# RxDuino_Rev4b.net
KiCad netlist of a schematic drawn in EAGLE
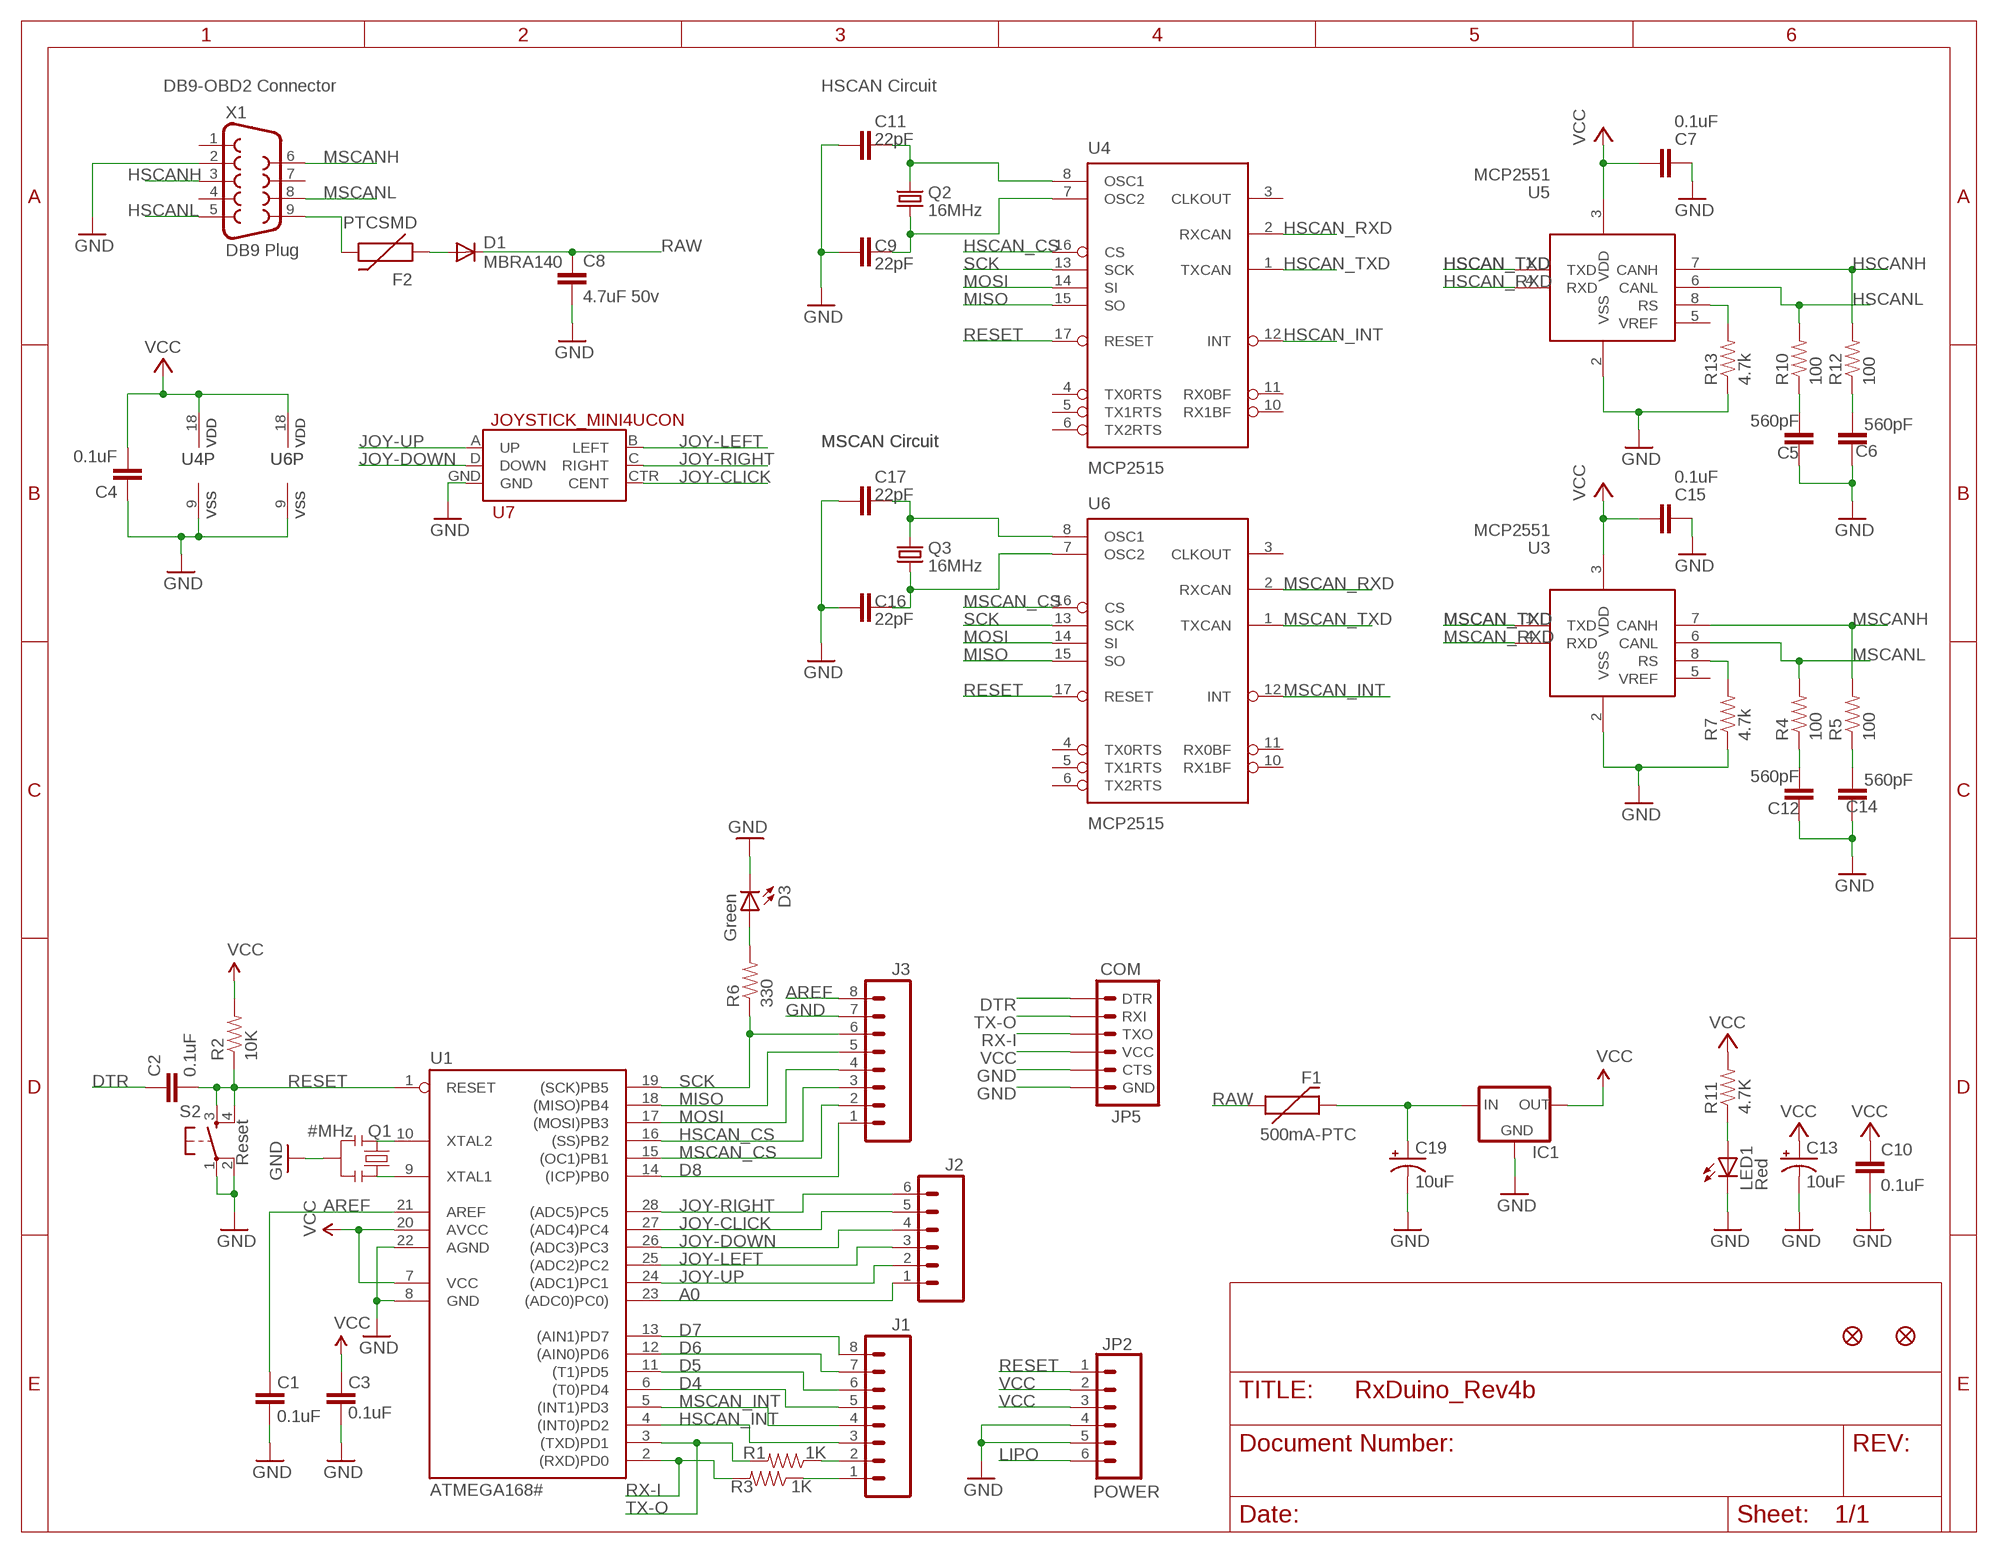
[diagram p0: schematic, sheet 1]

(export (version "E")
  (design (tool "Eeschema 10.0.6"))
  (components
    (comp (ref "C1")
      (value "0.1uF")
      (footprint "eagle-import:1206")
      (libsource (lib "eagle-import") (part "CAP1206"))
    )
    (comp (ref "C2")
      (value "0.1uF")
      (footprint "eagle-import:1206")
      (libsource (lib "eagle-import") (part "CAP1206"))
    )
    (comp (ref "C3")
      (value "0.1uF")
      (footprint "eagle-import:1206")
      (libsource (lib "eagle-import") (part "CAP1206"))
    )
    (comp (ref "C4")
      (value "0.1uF")
      (footprint "eagle-import:1206")
      (libsource (lib "eagle-import") (part "CAP1206"))
    )
    (comp (ref "C5")
      (value "560pF")
      (footprint "eagle-import:1206")
      (libsource (lib "eagle-import") (part "CAP1206"))
    )
    (comp (ref "C6")
      (value "560pF")
      (footprint "eagle-import:1206")
      (libsource (lib "eagle-import") (part "CAP1206"))
    )
    (comp (ref "C7")
      (value "0.1uF")
      (footprint "eagle-import:1206")
      (libsource (lib "eagle-import") (part "CAP1206"))
    )
    (comp (ref "C8")
      (value "4.7uF 50v")
      (footprint "eagle-import:1206")
      (libsource (lib "eagle-import") (part "CAP1206"))
    )
    (comp (ref "C9")
      (value "22pF")
      (footprint "eagle-import:1206")
      (libsource (lib "eagle-import") (part "CAP1206"))
    )
    (comp (ref "C10")
      (value "0.1uF")
      (footprint "eagle-import:1206")
      (libsource (lib "eagle-import") (part "CAP1206"))
    )
    (comp (ref "C11")
      (value "22pF")
      (footprint "eagle-import:1206")
      (libsource (lib "eagle-import") (part "CAP1206"))
    )
    (comp (ref "C12")
      (value "560pF")
      (footprint "eagle-import:1206")
      (libsource (lib "eagle-import") (part "CAP1206"))
    )
    (comp (ref "C13")
      (value "10uF")
      (footprint "eagle-import:PANASONIC_E")
      (libsource (lib "eagle-import") (part "CAP_POLE"))
    )
    (comp (ref "C14")
      (value "560pF")
      (footprint "eagle-import:1206")
      (libsource (lib "eagle-import") (part "CAP1206"))
    )
    (comp (ref "C15")
      (value "0.1uF")
      (footprint "eagle-import:1206")
      (libsource (lib "eagle-import") (part "CAP1206"))
    )
    (comp (ref "C16")
      (value "22pF")
      (footprint "eagle-import:1206")
      (libsource (lib "eagle-import") (part "CAP1206"))
    )
    (comp (ref "C17")
      (value "22pF")
      (footprint "eagle-import:1206")
      (libsource (lib "eagle-import") (part "CAP1206"))
    )
    (comp (ref "C19")
      (value "10uF")
      (footprint "eagle-import:PANASONIC_E")
      (libsource (lib "eagle-import") (part "CAP_POLE"))
    )
    (comp (ref "D1")
      (value "MBRA140")
      (footprint "eagle-import:SMA-DIODE")
      (libsource (lib "eagle-import") (part "DIODESMA"))
    )
    (comp (ref "D3")
      (value "Green")
      (footprint "eagle-import:LED-1206")
      (libsource (lib "eagle-import") (part "LED1206"))
    )
    (comp (ref "F1")
      (value "500mA-PTC")
      (footprint "eagle-import:PTC-1206")
      (libsource (lib "eagle-import") (part "PTCSMD"))
    )
    (comp (ref "F2")
      (value "PTCSMD")
      (footprint "eagle-import:PTC-1206")
      (libsource (lib "eagle-import") (part "PTCSMD"))
    )
    (comp (ref "IC1")
      (value "V_REG_78XX-TO-220")
      (footprint "eagle-import:TO-220-ALT")
      (libsource (lib "eagle-import") (part "V_REG_78XX-TO-220"))
    )
    (comp (ref "J1")
      (value "M08")
      (footprint "eagle-import:1X08")
      (libsource (lib "eagle-import") (part "M08"))
    )
    (comp (ref "J2")
      (value "M06SIP")
      (footprint "eagle-import:1X06")
      (libsource (lib "eagle-import") (part "M06SIP"))
    )
    (comp (ref "J3")
      (value "M08")
      (footprint "eagle-import:1X08")
      (libsource (lib "eagle-import") (part "M08"))
    )
    (comp (ref "JP2")
      (value "POWER")
      (footprint "eagle-import:1X06")
      (libsource (lib "eagle-import") (part "M06SIP"))
    )
    (comp (ref "JP5")
      (value "COM")
      (footprint "eagle-import:1X06")
      (libsource (lib "eagle-import") (part "ARDUINO_SERIAL_PROGRAMPTH"))
    )
    (comp (ref "LED1")
      (value "Red")
      (footprint "eagle-import:LED-1206")
      (libsource (lib "eagle-import") (part "LED1206"))
    )
    (comp (ref "Q1")
      (value "#MHz")
      (footprint "eagle-import:RESONATOR-PTH")
      (libsource (lib "eagle-import") (part "RESONATORPTH"))
    )
    (comp (ref "Q2")
      (value "16MHz")
      (footprint "eagle-import:HC49US")
      (libsource (lib "eagle-import") (part "CRYSTALHC49US"))
    )
    (comp (ref "Q3")
      (value "16MHz")
      (footprint "eagle-import:HC49US")
      (libsource (lib "eagle-import") (part "CRYSTALHC49US"))
    )
    (comp (ref "R1")
      (value "1K")
      (footprint "eagle-import:1206")
      (libsource (lib "eagle-import") (part "RESISTOR1206"))
    )
    (comp (ref "R2")
      (value "10K")
      (footprint "eagle-import:1206")
      (libsource (lib "eagle-import") (part "RESISTOR1206"))
    )
    (comp (ref "R3")
      (value "1K")
      (footprint "eagle-import:1206")
      (libsource (lib "eagle-import") (part "RESISTOR1206"))
    )
    (comp (ref "R4")
      (value "100")
      (footprint "eagle-import:1206")
      (libsource (lib "eagle-import") (part "RESISTOR1206"))
    )
    (comp (ref "R5")
      (value "100")
      (footprint "eagle-import:1206")
      (libsource (lib "eagle-import") (part "RESISTOR1206"))
    )
    (comp (ref "R6")
      (value "330")
      (footprint "eagle-import:1206")
      (libsource (lib "eagle-import") (part "RESISTOR1206"))
    )
    (comp (ref "R7")
      (value "4.7k")
      (footprint "eagle-import:1206")
      (libsource (lib "eagle-import") (part "RESISTOR1206"))
    )
    (comp (ref "R10")
      (value "100")
      (footprint "eagle-import:1206")
      (libsource (lib "eagle-import") (part "RESISTOR1206"))
    )
    (comp (ref "R11")
      (value "4.7K")
      (footprint "eagle-import:1206")
      (libsource (lib "eagle-import") (part "RESISTOR1206"))
    )
    (comp (ref "R12")
      (value "100")
      (footprint "eagle-import:1206")
      (libsource (lib "eagle-import") (part "RESISTOR1206"))
    )
    (comp (ref "R13")
      (value "4.7k")
      (footprint "eagle-import:1206")
      (libsource (lib "eagle-import") (part "RESISTOR1206"))
    )
    (comp (ref "S2")
      (value "Reset")
      (footprint "eagle-import:TACTILE_SWITCH_SMD")
      (libsource (lib "eagle-import") (part "TAC_SWITCHSND"))
    )
    (comp (ref "U$2")
      (value "FIDUCIAL1X2")
      (footprint "eagle-import:FIDUCIAL-1X2")
      (libsource (lib "eagle-import") (part "FIDUCIAL1X2"))
    )
    (comp (ref "U$4")
      (value "FIDUCIAL1X2")
      (footprint "eagle-import:FIDUCIAL-1X2")
      (libsource (lib "eagle-import") (part "FIDUCIAL1X2"))
    )
    (comp (ref "U1")
      (value "ATMEGA168#")
      (footprint "eagle-import:DIL28-3")
      (libsource (lib "eagle-import") (part "AT90S4433P"))
    )
    (comp (ref "U3")
      (value "MCP2551")
      (footprint "eagle-import:SO-08M")
      (libsource (lib "eagle-import") (part "MCP2551"))
    )
    (comp (ref "U4")
      (value "MCP2515")
      (footprint "eagle-import:SO-18W")
      (libsource (lib "eagle-import") (part "MCP2510SO"))
    )
    (comp (ref "U5")
      (value "MCP2551")
      (footprint "eagle-import:SO-08M")
      (libsource (lib "eagle-import") (part "MCP2551"))
    )
    (comp (ref "U6")
      (value "MCP2515")
      (footprint "eagle-import:SO-18W")
      (libsource (lib "eagle-import") (part "MCP2510SO"))
    )
    (comp (ref "U7")
      (value "JOYSTICK_MINI4UCON")
      (footprint "eagle-import:JOYSTICK_MINI")
      (libsource (lib "eagle-import") (part "JOYSTICK_MINI4UCON"))
    )
    (comp (ref "X1")
      (value "DB9 Plug")
      (footprint "eagle-import:DB9_MALE")
      (libsource (lib "eagle-import") (part "DB9MALE"))
    )
  )
  (nets
    (net (code "1") (name "/A0") (class "Default")
      (node (ref "J2") (pin "1") (pinfunction "1_1") (pintype "passive"))
      (node (ref "U1") (pin "23") (pinfunction "(ADC0)PC0)_23") (pintype "bidirectional"))
    )
    (net (code "2") (name "/AREF") (class "Default")
      (node (ref "C1") (pin "2") (pinfunction "2_2") (pintype "passive"))
      (node (ref "J3") (pin "8") (pinfunction "8_8") (pintype "passive"))
      (node (ref "U1") (pin "21") (pinfunction "AREF_21") (pintype "power_in"))
    )
    (net (code "3") (name "/D4") (class "Default")
      (node (ref "J1") (pin "5") (pinfunction "5_5") (pintype "passive"))
      (node (ref "U1") (pin "6") (pinfunction "(T0)PD4_6") (pintype "bidirectional"))
    )
    (net (code "4") (name "/D5") (class "Default")
      (node (ref "J1") (pin "6") (pinfunction "6_6") (pintype "passive"))
      (node (ref "U1") (pin "11") (pinfunction "(T1)PD5_11") (pintype "bidirectional"))
    )
    (net (code "5") (name "/D6") (class "Default")
      (node (ref "J1") (pin "7") (pinfunction "7_7") (pintype "passive"))
      (node (ref "U1") (pin "12") (pinfunction "(AIN0)PD6_12") (pintype "bidirectional"))
    )
    (net (code "6") (name "/D7") (class "Default")
      (node (ref "J1") (pin "8") (pinfunction "8_8") (pintype "passive"))
      (node (ref "U1") (pin "13") (pinfunction "(AIN1)PD7_13") (pintype "bidirectional"))
    )
    (net (code "7") (name "/D8") (class "Default")
      (node (ref "J3") (pin "1") (pinfunction "1_1") (pintype "passive"))
      (node (ref "U1") (pin "14") (pinfunction "(ICP)PB0_14") (pintype "bidirectional"))
    )
    (net (code "8") (name "/DTR") (class "Default")
      (node (ref "C2") (pin "1") (pinfunction "1_1") (pintype "passive"))
      (node (ref "JP5") (pin "1") (pinfunction "DTR_1") (pintype "passive"))
    )
    (net (code "9") (name "/HSCANH") (class "Default")
      (node (ref "R12") (pin "2") (pinfunction "2_2") (pintype "passive"))
      (node (ref "U5") (pin "7") (pinfunction "CANH_7") (pintype "bidirectional"))
      (node (ref "X1") (pin "3") (pinfunction "3_3") (pintype "passive"))
    )
    (net (code "10") (name "/HSCANL") (class "Default")
      (node (ref "R10") (pin "2") (pinfunction "2_2") (pintype "passive"))
      (node (ref "U5") (pin "6") (pinfunction "CANL_6") (pintype "bidirectional"))
      (node (ref "X1") (pin "5") (pinfunction "5_5") (pintype "passive"))
    )
    (net (code "11") (name "/HSCAN_CS") (class "Default")
      (node (ref "J3") (pin "3") (pinfunction "3_3") (pintype "passive"))
      (node (ref "U1") (pin "16") (pinfunction "(SS)PB2_16") (pintype "bidirectional"))
      (node (ref "U4") (pin "16") (pinfunction "CS_16") (pintype "input"))
    )
    (net (code "12") (name "/HSCAN_INT") (class "Default")
      (node (ref "J1") (pin "3") (pinfunction "3_3") (pintype "passive"))
      (node (ref "U1") (pin "4") (pinfunction "(INT0)PD2_4") (pintype "bidirectional"))
      (node (ref "U4") (pin "12") (pinfunction "INT_12") (pintype "output"))
    )
    (net (code "13") (name "/HSCAN_RXD") (class "Default")
      (node (ref "U4") (pin "2") (pinfunction "RXCAN_2") (pintype "input"))
      (node (ref "U5") (pin "4") (pinfunction "RXD_4") (pintype "bidirectional"))
    )
    (net (code "14") (name "/HSCAN_TXD") (class "Default")
      (node (ref "U4") (pin "1") (pinfunction "TXCAN_1") (pintype "output"))
      (node (ref "U5") (pin "1") (pinfunction "TXD_1") (pintype "bidirectional"))
    )
    (net (code "15") (name "/JOY-CLICK") (class "Default")
      (node (ref "J2") (pin "5") (pinfunction "5_5") (pintype "passive"))
      (node (ref "U1") (pin "27") (pinfunction "(ADC4)PC4_27") (pintype "bidirectional"))
      (node (ref "U7") (pin "CTR") (pinfunction "CENT_CTR") (pintype "bidirectional"))
    )
    (net (code "16") (name "/JOY-DOWN") (class "Default")
      (node (ref "J2") (pin "4") (pinfunction "4_4") (pintype "passive"))
      (node (ref "U1") (pin "26") (pinfunction "(ADC3)PC3_26") (pintype "bidirectional"))
      (node (ref "U7") (pin "D") (pinfunction "DOWN_D") (pintype "bidirectional"))
    )
    (net (code "17") (name "/JOY-LEFT") (class "Default")
      (node (ref "J2") (pin "3") (pinfunction "3_3") (pintype "passive"))
      (node (ref "U1") (pin "25") (pinfunction "(ADC2)PC2_25") (pintype "bidirectional"))
      (node (ref "U7") (pin "B") (pinfunction "LEFT_B") (pintype "bidirectional"))
    )
    (net (code "18") (name "/JOY-RIGHT") (class "Default")
      (node (ref "J2") (pin "6") (pinfunction "6_6") (pintype "passive"))
      (node (ref "U1") (pin "28") (pinfunction "(ADC5)PC5_28") (pintype "bidirectional"))
      (node (ref "U7") (pin "C") (pinfunction "RIGHT_C") (pintype "bidirectional"))
    )
    (net (code "19") (name "/JOY-UP") (class "Default")
      (node (ref "J2") (pin "2") (pinfunction "2_2") (pintype "passive"))
      (node (ref "U1") (pin "24") (pinfunction "(ADC1)PC1_24") (pintype "bidirectional"))
      (node (ref "U7") (pin "A") (pinfunction "UP_A") (pintype "bidirectional"))
    )
    (net (code "20") (name "/LIPO") (class "Default")
      (node (ref "JP2") (pin "6") (pinfunction "6_6") (pintype "passive"))
    )
    (net (code "21") (name "/MISO") (class "Default")
      (node (ref "J3") (pin "5") (pinfunction "5_5") (pintype "passive"))
      (node (ref "U1") (pin "18") (pinfunction "(MISO)PB4_18") (pintype "bidirectional"))
      (node (ref "U4") (pin "15") (pinfunction "SO_15") (pintype "output"))
      (node (ref "U6") (pin "15") (pinfunction "SO_15") (pintype "output"))
    )
    (net (code "22") (name "/MOSI") (class "Default")
      (node (ref "J3") (pin "4") (pinfunction "4_4") (pintype "passive"))
      (node (ref "U1") (pin "17") (pinfunction "(MOSI)PB3_17") (pintype "bidirectional"))
      (node (ref "U4") (pin "14") (pinfunction "SI_14") (pintype "input"))
      (node (ref "U6") (pin "14") (pinfunction "SI_14") (pintype "input"))
    )
    (net (code "23") (name "/MSCANH") (class "Default")
      (node (ref "R5") (pin "2") (pinfunction "2_2") (pintype "passive"))
      (node (ref "U3") (pin "7") (pinfunction "CANH_7") (pintype "bidirectional"))
      (node (ref "X1") (pin "6") (pinfunction "6_6") (pintype "passive"))
    )
    (net (code "24") (name "/MSCANL") (class "Default")
      (node (ref "R4") (pin "2") (pinfunction "2_2") (pintype "passive"))
      (node (ref "U3") (pin "6") (pinfunction "CANL_6") (pintype "bidirectional"))
      (node (ref "X1") (pin "8") (pinfunction "8_8") (pintype "passive"))
    )
    (net (code "25") (name "/MSCAN_CS") (class "Default")
      (node (ref "J3") (pin "2") (pinfunction "2_2") (pintype "passive"))
      (node (ref "U1") (pin "15") (pinfunction "(OC1)PB1_15") (pintype "bidirectional"))
      (node (ref "U6") (pin "16") (pinfunction "CS_16") (pintype "input"))
    )
    (net (code "26") (name "/MSCAN_INT") (class "Default")
      (node (ref "J1") (pin "4") (pinfunction "4_4") (pintype "passive"))
      (node (ref "U1") (pin "5") (pinfunction "(INT1)PD3_5") (pintype "bidirectional"))
      (node (ref "U6") (pin "12") (pinfunction "INT_12") (pintype "output"))
    )
    (net (code "27") (name "/MSCAN_RXD") (class "Default")
      (node (ref "U3") (pin "4") (pinfunction "RXD_4") (pintype "bidirectional"))
      (node (ref "U6") (pin "2") (pinfunction "RXCAN_2") (pintype "input"))
    )
    (net (code "28") (name "/MSCAN_TXD") (class "Default")
      (node (ref "U3") (pin "1") (pinfunction "TXD_1") (pintype "bidirectional"))
      (node (ref "U6") (pin "1") (pinfunction "TXCAN_1") (pintype "output"))
    )
    (net (code "29") (name "/RAW") (class "Default")
      (node (ref "C8") (pin "1") (pinfunction "1_1") (pintype "passive"))
      (node (ref "D1") (pin "C") (pinfunction "C_C") (pintype "passive"))
      (node (ref "F1") (pin "1") (pinfunction "1_1") (pintype "bidirectional"))
    )
    (net (code "30") (name "/RESET") (class "Default")
      (node (ref "C2") (pin "2") (pinfunction "2_2") (pintype "passive"))
      (node (ref "JP2") (pin "1") (pinfunction "1_1") (pintype "passive"))
      (node (ref "R2") (pin "1") (pinfunction "1_1") (pintype "passive"))
      (node (ref "S2") (pin "3") (pinfunction "3_3") (pintype "passive"))
      (node (ref "S2") (pin "4") (pinfunction "4_4") (pintype "passive"))
      (node (ref "U1") (pin "1") (pinfunction "RESET_1") (pintype "input"))
      (node (ref "U4") (pin "17") (pinfunction "RESET_17") (pintype "input"))
      (node (ref "U6") (pin "17") (pinfunction "RESET_17") (pintype "input"))
    )
    (net (code "31") (name "/RX-I") (class "Default")
      (node (ref "JP5") (pin "3") (pinfunction "TXO_3") (pintype "passive"))
      (node (ref "R3") (pin "2") (pinfunction "2_2") (pintype "passive"))
      (node (ref "U1") (pin "2") (pinfunction "(RXD)PD0_2") (pintype "bidirectional"))
    )
    (net (code "32") (name "/SCK") (class "Default")
      (node (ref "J3") (pin "6") (pinfunction "6_6") (pintype "passive"))
      (node (ref "R6") (pin "1") (pinfunction "1_1") (pintype "passive"))
      (node (ref "U1") (pin "19") (pinfunction "(SCK)PB5_19") (pintype "bidirectional"))
      (node (ref "U4") (pin "13") (pinfunction "SCK_13") (pintype "input"))
      (node (ref "U6") (pin "13") (pinfunction "SCK_13") (pintype "input"))
    )
    (net (code "33") (name "/TX-O") (class "Default")
      (node (ref "JP5") (pin "2") (pinfunction "RXI_2") (pintype "passive"))
      (node (ref "R1") (pin "2") (pinfunction "2_2") (pintype "passive"))
      (node (ref "U1") (pin "3") (pinfunction "(TXD)PD1_3") (pintype "bidirectional"))
    )
    (net (code "34") (name "GND") (class "Default")
      (node (ref "C1") (pin "1") (pinfunction "1_1") (pintype "passive"))
      (node (ref "C10") (pin "2") (pinfunction "2_2") (pintype "passive"))
      (node (ref "C11") (pin "1") (pinfunction "1_1") (pintype "passive"))
      (node (ref "C12") (pin "1") (pinfunction "1_1") (pintype "passive"))
      (node (ref "C13") (pin "-") (pinfunction "-_-") (pintype "passive"))
      (node (ref "C14") (pin "1") (pinfunction "1_1") (pintype "passive"))
      (node (ref "C15") (pin "1") (pinfunction "1_1") (pintype "passive"))
      (node (ref "C16") (pin "1") (pinfunction "1_1") (pintype "passive"))
      (node (ref "C17") (pin "1") (pinfunction "1_1") (pintype "passive"))
      (node (ref "C19") (pin "-") (pinfunction "-_-") (pintype "passive"))
      (node (ref "C3") (pin "1") (pinfunction "1_1") (pintype "passive"))
      (node (ref "C4") (pin "1") (pinfunction "1_1") (pintype "passive"))
      (node (ref "C5") (pin "1") (pinfunction "1_1") (pintype "passive"))
      (node (ref "C6") (pin "1") (pinfunction "1_1") (pintype "passive"))
      (node (ref "C7") (pin "1") (pinfunction "1_1") (pintype "passive"))
      (node (ref "C8") (pin "2") (pinfunction "2_2") (pintype "passive"))
      (node (ref "C9") (pin "1") (pinfunction "1_1") (pintype "passive"))
      (node (ref "D3") (pin "C") (pinfunction "C_C") (pintype "passive"))
      (node (ref "IC1") (pin "GND") (pinfunction "GND_GND") (pintype "input"))
      (node (ref "J3") (pin "7") (pinfunction "7_7") (pintype "passive"))
      (node (ref "JP2") (pin "4") (pinfunction "4_4") (pintype "passive"))
      (node (ref "JP2") (pin "5") (pinfunction "5_5") (pintype "passive"))
      (node (ref "JP5") (pin "5") (pinfunction "CTS_5") (pintype "passive"))
      (node (ref "JP5") (pin "6") (pinfunction "GND_6") (pintype "passive"))
      (node (ref "LED1") (pin "C") (pinfunction "C_C") (pintype "passive"))
      (node (ref "Q1") (pin "2") (pinfunction "2_2") (pintype "passive"))
      (node (ref "R13") (pin "1") (pinfunction "1_1") (pintype "passive"))
      (node (ref "R7") (pin "1") (pinfunction "1_1") (pintype "passive"))
      (node (ref "S2") (pin "1") (pinfunction "1_1") (pintype "passive"))
      (node (ref "S2") (pin "2") (pinfunction "2_2") (pintype "passive"))
      (node (ref "U1") (pin "22") (pinfunction "AGND_22") (pintype "power_in"))
      (node (ref "U1") (pin "8") (pinfunction "GND_8") (pintype "power_in"))
      (node (ref "U3") (pin "2") (pinfunction "VSS_2") (pintype "power_in"))
      (node (ref "U4") (pin "9") (pinfunction "VSS_9") (pintype "power_in"))
      (node (ref "U5") (pin "2") (pinfunction "VSS_2") (pintype "power_in"))
      (node (ref "U6") (pin "9") (pinfunction "VSS_9") (pintype "power_in"))
      (node (ref "U7") (pin "GND") (pinfunction "GND_GND") (pintype "bidirectional"))
      (node (ref "X1") (pin "2") (pinfunction "2_2") (pintype "passive"))
    )
    (net (code "35") (name "Net-(C5-Pad2)") (class "Default")
      (node (ref "C5") (pin "2") (pinfunction "2_2") (pintype "passive"))
      (node (ref "R10") (pin "1") (pinfunction "1_1") (pintype "passive"))
    )
    (net (code "36") (name "Net-(C6-Pad2)") (class "Default")
      (node (ref "C6") (pin "2") (pinfunction "2_2") (pintype "passive"))
      (node (ref "R12") (pin "1") (pinfunction "1_1") (pintype "passive"))
    )
    (net (code "37") (name "Net-(C12-Pad2)") (class "Default")
      (node (ref "C12") (pin "2") (pinfunction "2_2") (pintype "passive"))
      (node (ref "R4") (pin "1") (pinfunction "1_1") (pintype "passive"))
    )
    (net (code "38") (name "Net-(C14-Pad2)") (class "Default")
      (node (ref "C14") (pin "2") (pinfunction "2_2") (pintype "passive"))
      (node (ref "R5") (pin "1") (pinfunction "1_1") (pintype "passive"))
    )
    (net (code "39") (name "Net-(C19-Pad+)") (class "Default")
      (node (ref "C19") (pin "+") (pinfunction "+_+") (pintype "passive"))
      (node (ref "F1") (pin "2") (pinfunction "2_2") (pintype "bidirectional"))
      (node (ref "IC1") (pin "IN") (pinfunction "IN_IN") (pintype "input"))
    )
    (net (code "40") (name "Net-(D1-PadA)") (class "Default")
      (node (ref "D1") (pin "A") (pinfunction "A_A") (pintype "passive"))
      (node (ref "F2") (pin "1") (pinfunction "1_1") (pintype "bidirectional"))
    )
    (net (code "41") (name "Net-(D3-PadA)") (class "Default")
      (node (ref "D3") (pin "A") (pinfunction "A_A") (pintype "passive"))
      (node (ref "R6") (pin "2") (pinfunction "2_2") (pintype "passive"))
    )
    (net (code "42") (name "Net-(F2-Pad2)") (class "Default")
      (node (ref "F2") (pin "2") (pinfunction "2_2") (pintype "bidirectional"))
      (node (ref "X1") (pin "9") (pinfunction "9_9") (pintype "passive"))
    )
    (net (code "43") (name "Net-(J1-Pad1)") (class "Default")
      (node (ref "J1") (pin "1") (pinfunction "1_1") (pintype "passive"))
      (node (ref "R3") (pin "1") (pinfunction "1_1") (pintype "passive"))
    )
    (net (code "44") (name "Net-(J1-Pad2)") (class "Default")
      (node (ref "J1") (pin "2") (pinfunction "2_2") (pintype "passive"))
      (node (ref "R1") (pin "1") (pinfunction "1_1") (pintype "passive"))
    )
    (net (code "45") (name "Net-(LED1-PadA)") (class "Default")
      (node (ref "LED1") (pin "A") (pinfunction "A_A") (pintype "passive"))
      (node (ref "R11") (pin "1") (pinfunction "1_1") (pintype "passive"))
    )
    (net (code "46") (name "Net-(U1-XTAL1)") (class "Default")
      (node (ref "Q1") (pin "3") (pinfunction "3_3") (pintype "passive"))
      (node (ref "U1") (pin "9") (pinfunction "XTAL1_9") (pintype "bidirectional"))
    )
    (net (code "47") (name "Net-(U1-XTAL2)") (class "Default")
      (node (ref "Q1") (pin "1") (pinfunction "1_1") (pintype "passive"))
      (node (ref "U1") (pin "10") (pinfunction "XTAL2_10") (pintype "bidirectional"))
    )
    (net (code "48") (name "Net-(U3-RS)") (class "Default")
      (node (ref "R7") (pin "2") (pinfunction "2_2") (pintype "passive"))
      (node (ref "U3") (pin "8") (pinfunction "RS_8") (pintype "bidirectional"))
    )
    (net (code "49") (name "Net-(U4A-OSC1)") (class "Default")
      (node (ref "C11") (pin "2") (pinfunction "2_2") (pintype "passive"))
      (node (ref "Q2") (pin "2") (pinfunction "2_2") (pintype "passive"))
      (node (ref "U4") (pin "8") (pinfunction "OSC1_8") (pintype "input"))
    )
    (net (code "50") (name "Net-(U4A-OSC2)") (class "Default")
      (node (ref "C9") (pin "2") (pinfunction "2_2") (pintype "passive"))
      (node (ref "Q2") (pin "1") (pinfunction "1_1") (pintype "passive"))
      (node (ref "U4") (pin "7") (pinfunction "OSC2_7") (pintype "output"))
    )
    (net (code "51") (name "Net-(U5-RS)") (class "Default")
      (node (ref "R13") (pin "2") (pinfunction "2_2") (pintype "passive"))
      (node (ref "U5") (pin "8") (pinfunction "RS_8") (pintype "bidirectional"))
    )
    (net (code "52") (name "Net-(U6A-OSC1)") (class "Default")
      (node (ref "C17") (pin "2") (pinfunction "2_2") (pintype "passive"))
      (node (ref "Q3") (pin "2") (pinfunction "2_2") (pintype "passive"))
      (node (ref "U6") (pin "8") (pinfunction "OSC1_8") (pintype "input"))
    )
    (net (code "53") (name "Net-(U6A-OSC2)") (class "Default")
      (node (ref "C16") (pin "2") (pinfunction "2_2") (pintype "passive"))
      (node (ref "Q3") (pin "1") (pinfunction "1_1") (pintype "passive"))
      (node (ref "U6") (pin "7") (pinfunction "OSC2_7") (pintype "output"))
    )
    (net (code "54") (name "VCC") (class "Default")
      (node (ref "C10") (pin "1") (pinfunction "1_1") (pintype "passive"))
      (node (ref "C13") (pin "+") (pinfunction "+_+") (pintype "passive"))
      (node (ref "C15") (pin "2") (pinfunction "2_2") (pintype "passive"))
      (node (ref "C3") (pin "2") (pinfunction "2_2") (pintype "passive"))
      (node (ref "C4") (pin "2") (pinfunction "2_2") (pintype "passive"))
      (node (ref "C7") (pin "2") (pinfunction "2_2") (pintype "passive"))
      (node (ref "IC1") (pin "OUT") (pinfunction "OUT_OUT") (pintype "output"))
      (node (ref "JP2") (pin "2") (pinfunction "2_2") (pintype "passive"))
      (node (ref "JP2") (pin "3") (pinfunction "3_3") (pintype "passive"))
      (node (ref "JP5") (pin "4") (pinfunction "VCC_4") (pintype "passive"))
      (node (ref "R11") (pin "2") (pinfunction "2_2") (pintype "passive"))
      (node (ref "R2") (pin "2") (pinfunction "2_2") (pintype "passive"))
      (node (ref "U1") (pin "20") (pinfunction "AVCC_20") (pintype "power_in"))
      (node (ref "U1") (pin "7") (pinfunction "VCC_7") (pintype "power_in"))
      (node (ref "U3") (pin "3") (pinfunction "VDD_3") (pintype "power_in"))
      (node (ref "U4") (pin "18") (pinfunction "VDD_18") (pintype "power_in"))
      (node (ref "U5") (pin "3") (pinfunction "VDD_3") (pintype "power_in"))
      (node (ref "U6") (pin "18") (pinfunction "VDD_18") (pintype "power_in"))
    )
    (net (code "55") (name "unconnected-(U3-VREF-Pad5)") (class "Default")
      (node (ref "U3") (pin "5") (pinfunction "VREF_5") (pintype "bidirectional"))
    )
    (net (code "56") (name "unconnected-(U4A-CLKOUT-Pad3)") (class "Default")
      (node (ref "U4") (pin "3") (pinfunction "CLKOUT_3") (pintype "output"))
    )
    (net (code "57") (name "unconnected-(U4A-RX0BF-Pad11)") (class "Default")
      (node (ref "U4") (pin "11") (pinfunction "RX0BF_11") (pintype "output"))
    )
    (net (code "58") (name "unconnected-(U4A-RX1BF-Pad10)") (class "Default")
      (node (ref "U4") (pin "10") (pinfunction "RX1BF_10") (pintype "output"))
    )
    (net (code "59") (name "unconnected-(U4A-TX0RTS-Pad4)") (class "Default")
      (node (ref "U4") (pin "4") (pinfunction "TX0RTS_4") (pintype "input"))
    )
    (net (code "60") (name "unconnected-(U4A-TX1RTS-Pad5)") (class "Default")
      (node (ref "U4") (pin "5") (pinfunction "TX1RTS_5") (pintype "input"))
    )
    (net (code "61") (name "unconnected-(U4A-TX2RTS-Pad6)") (class "Default")
      (node (ref "U4") (pin "6") (pinfunction "TX2RTS_6") (pintype "input"))
    )
    (net (code "62") (name "unconnected-(U5-VREF-Pad5)") (class "Default")
      (node (ref "U5") (pin "5") (pinfunction "VREF_5") (pintype "bidirectional"))
    )
    (net (code "63") (name "unconnected-(U6A-CLKOUT-Pad3)") (class "Default")
      (node (ref "U6") (pin "3") (pinfunction "CLKOUT_3") (pintype "output"))
    )
    (net (code "64") (name "unconnected-(U6A-RX0BF-Pad11)") (class "Default")
      (node (ref "U6") (pin "11") (pinfunction "RX0BF_11") (pintype "output"))
    )
    (net (code "65") (name "unconnected-(U6A-RX1BF-Pad10)") (class "Default")
      (node (ref "U6") (pin "10") (pinfunction "RX1BF_10") (pintype "output"))
    )
    (net (code "66") (name "unconnected-(U6A-TX0RTS-Pad4)") (class "Default")
      (node (ref "U6") (pin "4") (pinfunction "TX0RTS_4") (pintype "input"))
    )
    (net (code "67") (name "unconnected-(U6A-TX1RTS-Pad5)") (class "Default")
      (node (ref "U6") (pin "5") (pinfunction "TX1RTS_5") (pintype "input"))
    )
    (net (code "68") (name "unconnected-(U6A-TX2RTS-Pad6)") (class "Default")
      (node (ref "U6") (pin "6") (pinfunction "TX2RTS_6") (pintype "input"))
    )
    (net (code "69") (name "unconnected-(X1-Pad1)") (class "Default")
      (node (ref "X1") (pin "1") (pinfunction "1_1") (pintype "passive"))
    )
    (net (code "70") (name "unconnected-(X1-Pad4)") (class "Default")
      (node (ref "X1") (pin "4") (pinfunction "4_4") (pintype "passive"))
    )
    (net (code "71") (name "unconnected-(X1-Pad7)") (class "Default")
      (node (ref "X1") (pin "7") (pinfunction "7_7") (pintype "passive"))
    )
  )
)
